# handheld-telefon.net
KiCad netlist of a schematic drawn in EAGLE
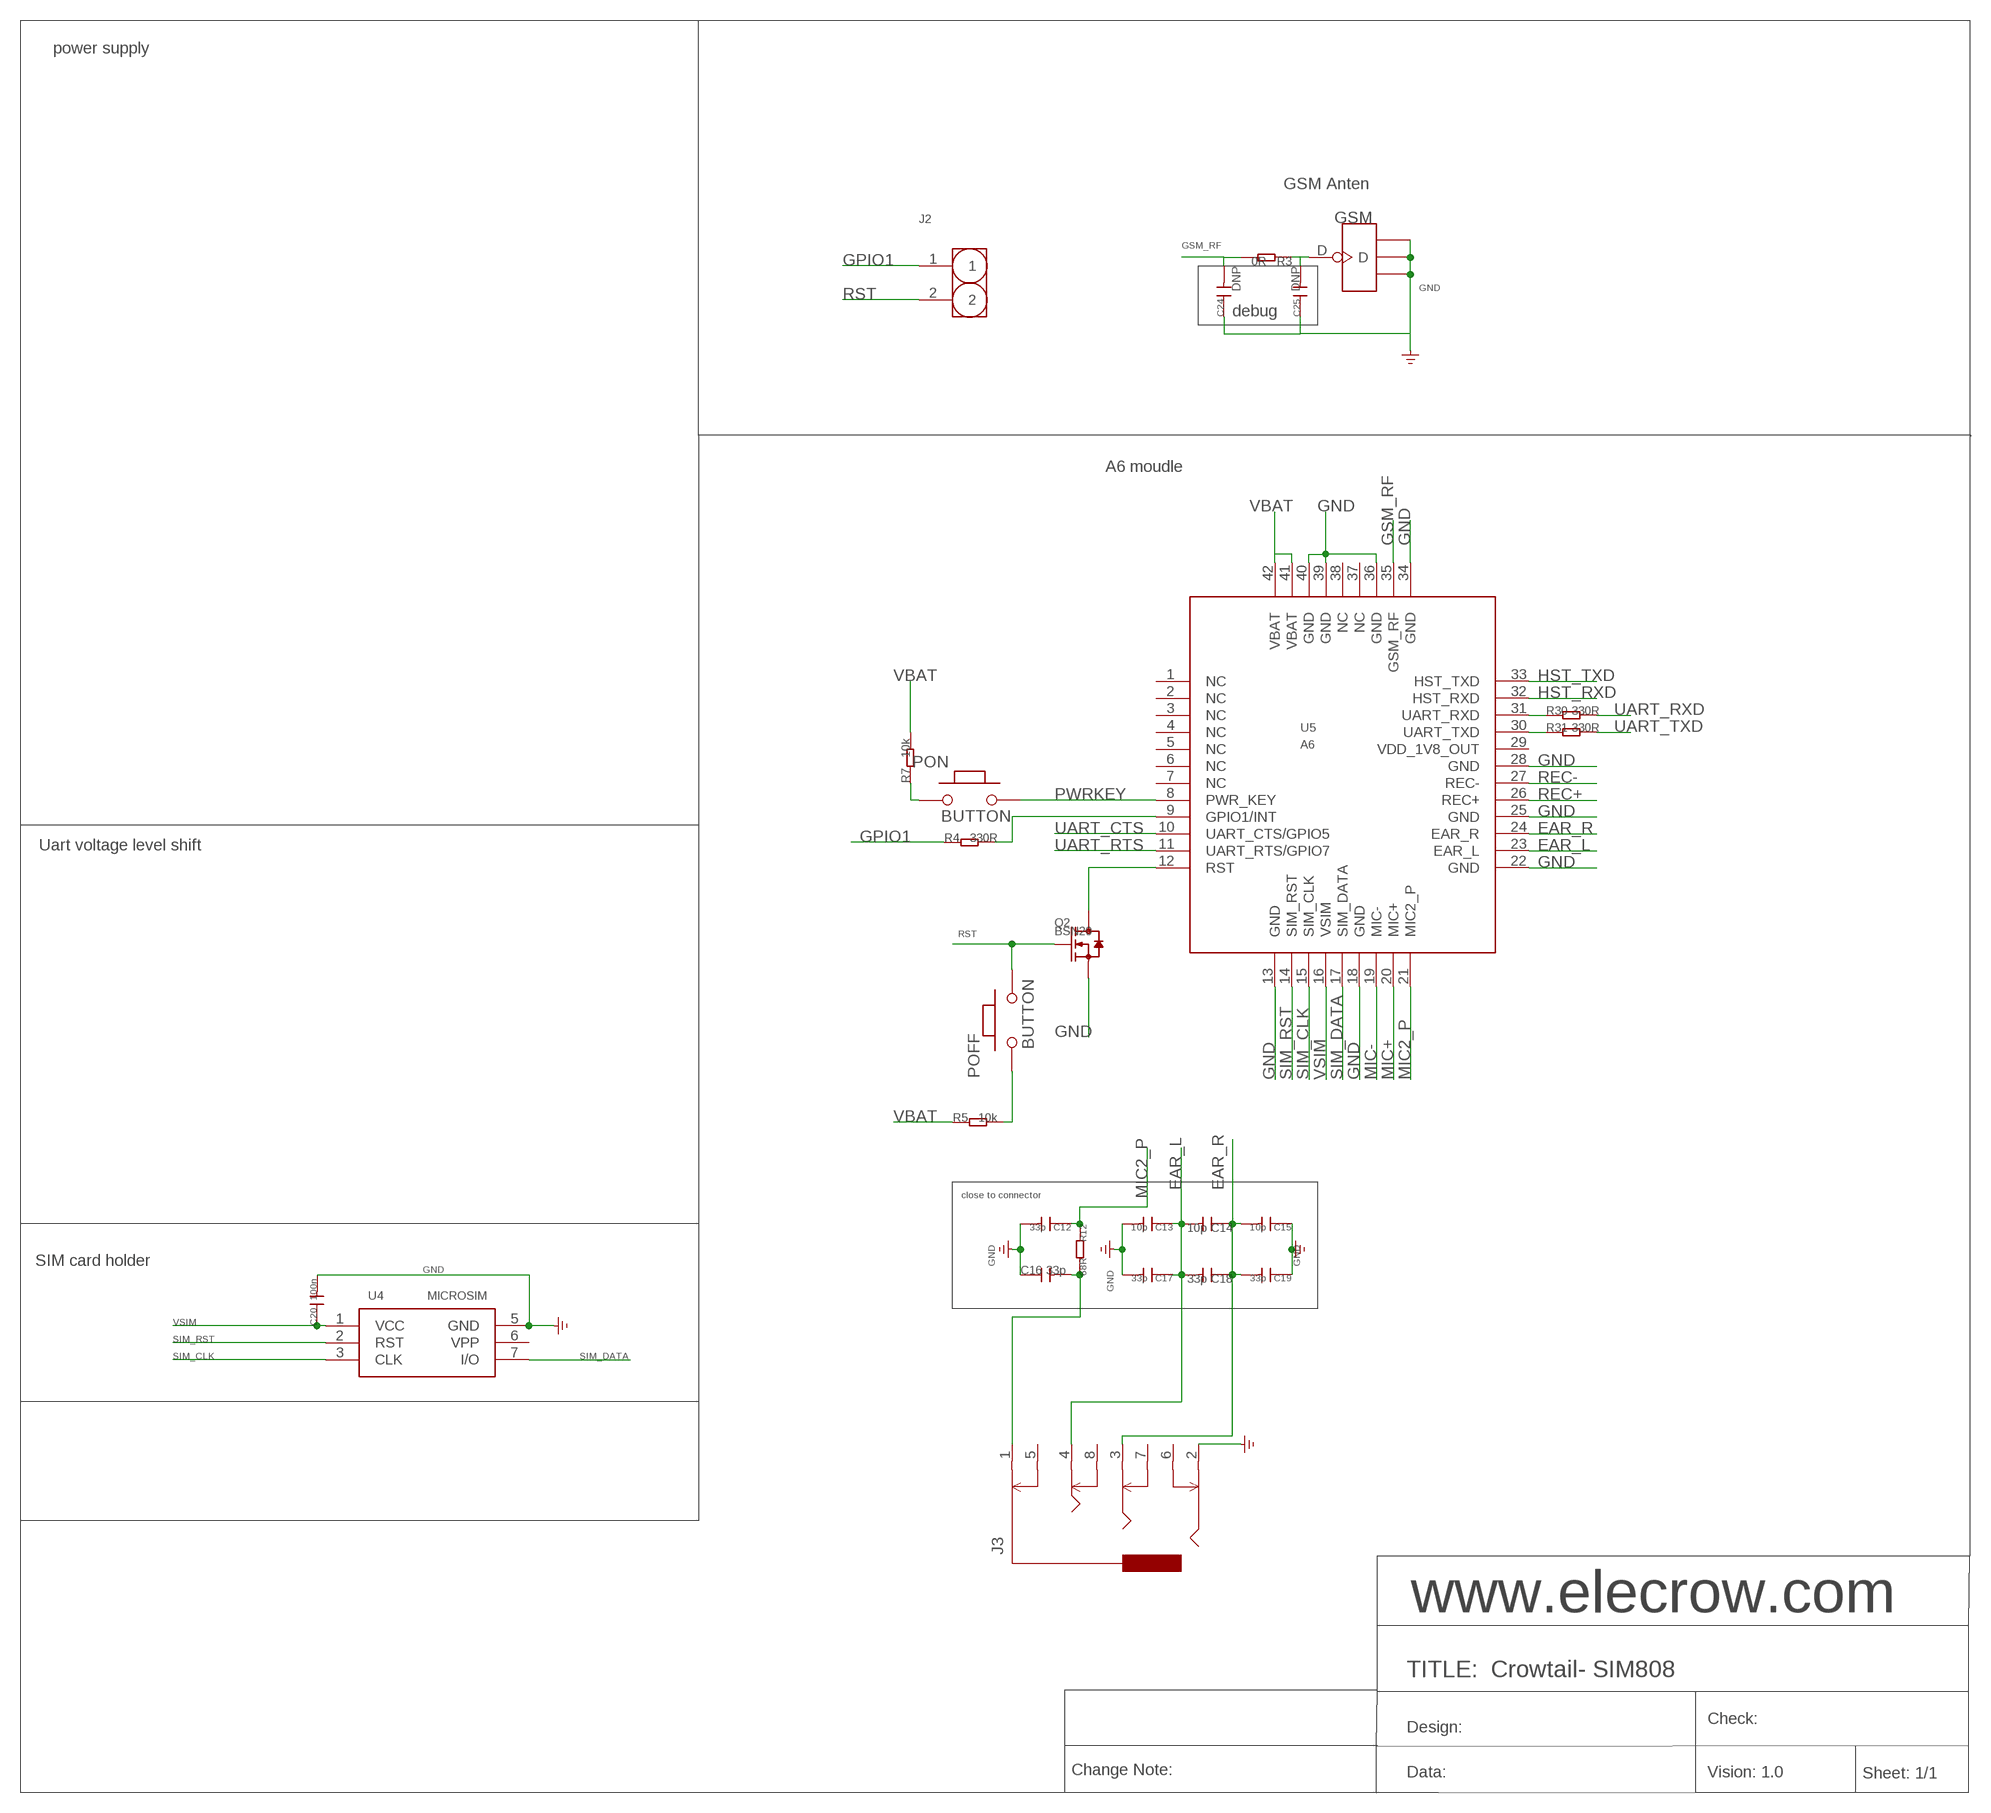
[diagram p0: schematic, sheet 1]

(export (version "E")
  (design (tool "Eeschema 10.0.6"))
  (components
    (comp (ref "C12")
      (value "33p")
      (footprint "eagle-import:C0603")
      (libsource (lib "eagle-import") (part "C-0603"))
    )
    (comp (ref "C13")
      (value "10p")
      (footprint "eagle-import:C0402")
      (libsource (lib "eagle-import") (part "C-0402"))
    )
    (comp (ref "C14")
      (value "10p")
      (footprint "eagle-import:C0402")
      (libsource (lib "eagle-import") (part "C-0402"))
    )
    (comp (ref "C15")
      (value "10p")
      (footprint "eagle-import:C0402")
      (libsource (lib "eagle-import") (part "C-0402"))
    )
    (comp (ref "C16")
      (value "33p")
      (footprint "eagle-import:C0603")
      (libsource (lib "eagle-import") (part "C-0603"))
    )
    (comp (ref "C17")
      (value "33p")
      (footprint "eagle-import:C0402")
      (libsource (lib "eagle-import") (part "C-0402"))
    )
    (comp (ref "C18")
      (value "33p")
      (footprint "eagle-import:C0402")
      (libsource (lib "eagle-import") (part "C-0402"))
    )
    (comp (ref "C19")
      (value "33p")
      (footprint "eagle-import:C0402")
      (libsource (lib "eagle-import") (part "C-0402"))
    )
    (comp (ref "C20")
      (value "100n")
      (footprint "eagle-import:C0603")
      (libsource (lib "eagle-import") (part "C-0603"))
    )
    (comp (ref "C24")
      (value "DNP")
      (footprint "eagle-import:C0402")
      (libsource (lib "eagle-import") (part "C-0402"))
    )
    (comp (ref "C25")
      (value "DNP")
      (footprint "eagle-import:C0402")
      (libsource (lib "eagle-import") (part "C-0402"))
    )
    (comp (ref "GSM")
      (value "ANTENNA-U-FL")
      (footprint "eagle-import:4P-U-FL")
      (libsource (lib "eagle-import") (part "ANTENNA-U-FL"))
    )
    (comp (ref "J2")
      (value "HEADER-2P-65/35MIL")
      (footprint "eagle-import:2P-2.54-65_35MIL")
      (libsource (lib "eagle-import") (part "HEADER-2P-65/35MIL"))
    )
    (comp (ref "J3")
      (value "AUDIO-8P'PJ-3536-L6S'")
      (footprint "eagle-import:8P-3.5-SMD")
      (libsource (lib "eagle-import") (part "AUDIO-8P'PJ-3536-L6S'"))
    )
    (comp (ref "POFF")
      (value "BUTTON")
      (footprint "eagle-import:157SW")
      (libsource (lib "eagle-import") (part "PB157"))
    )
    (comp (ref "PON")
      (value "BUTTON")
      (footprint "eagle-import:157SW")
      (libsource (lib "eagle-import") (part "PB157"))
    )
    (comp (ref "Q2")
      (value "BSN20")
      (footprint "eagle-import:SOT23")
      (libsource (lib "eagle-import") (part "MOSFET-N'SOT23'"))
    )
    (comp (ref "R3")
      (value "0R")
      (footprint "eagle-import:R0603")
      (libsource (lib "eagle-import") (part "R-0603"))
    )
    (comp (ref "R4")
      (value "330R")
      (footprint "eagle-import:R0603")
      (libsource (lib "eagle-import") (part "R-0603"))
    )
    (comp (ref "R5")
      (value "10k")
      (footprint "eagle-import:R0603")
      (libsource (lib "eagle-import") (part "R-0603"))
    )
    (comp (ref "R7")
      (value "10k")
      (footprint "eagle-import:R0603")
      (libsource (lib "eagle-import") (part "R-0603"))
    )
    (comp (ref "R12")
      (value "68R")
      (footprint "eagle-import:R0603")
      (libsource (lib "eagle-import") (part "R-0603"))
    )
    (comp (ref "R30")
      (value "330R")
      (footprint "eagle-import:R0603")
      (libsource (lib "eagle-import") (part "R-0603"))
    )
    (comp (ref "R31")
      (value "330R")
      (footprint "eagle-import:R0603")
      (libsource (lib "eagle-import") (part "R-0603"))
    )
    (comp (ref "U4")
      (value "MICROSIM")
      (footprint "eagle-import:MICROSIM")
      (libsource (lib "eagle-import") (part "MICROSIM"))
    )
    (comp (ref "U5") (value "A6") (footprint "eagle-import:A6") (libsource (lib "eagle-import") (part "A6")))
  )
  (nets
    (net (code "1") (name "/EAR_L") (class "Default")
      (node (ref "C13") (pin "1") (pinfunction "1_1") (pintype "passive"))
      (node (ref "C14") (pin "2") (pinfunction "2_2") (pintype "passive"))
      (node (ref "C17") (pin "1") (pinfunction "1_1") (pintype "passive"))
      (node (ref "C18") (pin "2") (pinfunction "2_2") (pintype "passive"))
      (node (ref "J3") (pin "4") (pinfunction "4_4") (pintype "bidirectional"))
      (node (ref "U5") (pin "23") (pinfunction "EAR_L_23") (pintype "bidirectional"))
    )
    (net (code "2") (name "/EAR_R") (class "Default")
      (node (ref "C14") (pin "1") (pinfunction "1_1") (pintype "passive"))
      (node (ref "C15") (pin "2") (pinfunction "2_2") (pintype "passive"))
      (node (ref "C18") (pin "1") (pinfunction "1_1") (pintype "passive"))
      (node (ref "C19") (pin "2") (pinfunction "2_2") (pintype "passive"))
      (node (ref "J3") (pin "3") (pinfunction "3_3") (pintype "bidirectional"))
      (node (ref "U5") (pin "24") (pinfunction "EAR_R_24") (pintype "bidirectional"))
    )
    (net (code "3") (name "/GPIO1") (class "Default")
      (node (ref "J2") (pin "1") (pinfunction "1_1") (pintype "bidirectional"))
      (node (ref "R4") (pin "1") (pinfunction "1_1") (pintype "passive"))
    )
    (net (code "4") (name "/GSM_RF") (class "Default")
      (node (ref "C24") (pin "2") (pinfunction "2_2") (pintype "passive"))
      (node (ref "R3") (pin "2") (pinfunction "2_2") (pintype "passive"))
      (node (ref "U5") (pin "35") (pinfunction "GSM_RF_35") (pintype "bidirectional"))
    )
    (net (code "5") (name "/HST_RXD") (class "Default")
      (node (ref "U5") (pin "32") (pinfunction "HST_RXD_32") (pintype "bidirectional"))
    )
    (net (code "6") (name "/HST_TXD") (class "Default")
      (node (ref "U5") (pin "33") (pinfunction "HST_TXD_33") (pintype "bidirectional"))
    )
    (net (code "7") (name "/MIC+") (class "Default")
      (node (ref "U5") (pin "20") (pinfunction "MIC+_20") (pintype "bidirectional"))
    )
    (net (code "8") (name "/MIC-") (class "Default")
      (node (ref "U5") (pin "19") (pinfunction "MIC-_19") (pintype "bidirectional"))
    )
    (net (code "9") (name "/MIC2_P") (class "Default")
      (node (ref "C12") (pin "1") (pinfunction "1_1") (pintype "passive"))
      (node (ref "R12") (pin "1") (pinfunction "1_1") (pintype "passive"))
      (node (ref "U5") (pin "21") (pinfunction "MIC2_P_21") (pintype "bidirectional"))
    )
    (net (code "10") (name "/PWRKEY") (class "Default")
      (node (ref "PON") (pin "2") (pinfunction "2_2") (pintype "passive"))
      (node (ref "U5") (pin "8") (pinfunction "PWR_KEY_8") (pintype "bidirectional"))
    )
    (net (code "11") (name "/REC+") (class "Default")
      (node (ref "U5") (pin "26") (pinfunction "REC+_26") (pintype "bidirectional"))
    )
    (net (code "12") (name "/REC-") (class "Default")
      (node (ref "U5") (pin "27") (pinfunction "REC-_27") (pintype "bidirectional"))
    )
    (net (code "13") (name "/RST") (class "Default")
      (node (ref "J2") (pin "2") (pinfunction "2_2") (pintype "bidirectional"))
      (node (ref "POFF") (pin "2") (pinfunction "2_2") (pintype "passive"))
      (node (ref "Q2") (pin "1") (pinfunction "G_1") (pintype "passive"))
    )
    (net (code "14") (name "/SIM_CLK") (class "Default")
      (node (ref "U4") (pin "3") (pinfunction "CLK_3") (pintype "bidirectional"))
      (node (ref "U5") (pin "15") (pinfunction "SIM_CLK_15") (pintype "bidirectional"))
    )
    (net (code "15") (name "/SIM_DATA") (class "Default")
      (node (ref "U4") (pin "7") (pinfunction "I/O_7") (pintype "bidirectional"))
      (node (ref "U5") (pin "17") (pinfunction "SIM_DATA_17") (pintype "bidirectional"))
    )
    (net (code "16") (name "/SIM_RST") (class "Default")
      (node (ref "U4") (pin "2") (pinfunction "RST_2") (pintype "bidirectional"))
      (node (ref "U5") (pin "14") (pinfunction "SIM_RST_14") (pintype "bidirectional"))
    )
    (net (code "17") (name "/UART_CTS") (class "Default")
      (node (ref "U5") (pin "10") (pinfunction "UART_CTS/GPIO5_10") (pintype "bidirectional"))
    )
    (net (code "18") (name "/UART_RTS") (class "Default")
      (node (ref "U5") (pin "11") (pinfunction "UART_RTS/GPIO7_11") (pintype "bidirectional"))
    )
    (net (code "19") (name "/UART_RXD") (class "Default")
      (node (ref "R30") (pin "2") (pinfunction "2_2") (pintype "passive"))
    )
    (net (code "20") (name "/UART_TXD") (class "Default")
      (node (ref "R31") (pin "2") (pinfunction "2_2") (pintype "passive"))
    )
    (net (code "21") (name "/VBAT") (class "Default")
      (node (ref "R5") (pin "1") (pinfunction "1_1") (pintype "passive"))
      (node (ref "R7") (pin "2") (pinfunction "2_2") (pintype "passive"))
      (node (ref "U5") (pin "41") (pinfunction "VBAT_41") (pintype "bidirectional"))
      (node (ref "U5") (pin "42") (pinfunction "VBAT_42") (pintype "bidirectional"))
    )
    (net (code "22") (name "/VSIM") (class "Default")
      (node (ref "C20") (pin "1") (pinfunction "1_1") (pintype "passive"))
      (node (ref "U4") (pin "1") (pinfunction "VCC_1") (pintype "bidirectional"))
      (node (ref "U5") (pin "16") (pinfunction "VSIM_16") (pintype "bidirectional"))
    )
    (net (code "23") (name "GND_POWER") (class "Default")
      (node (ref "C12") (pin "2") (pinfunction "2_2") (pintype "passive"))
      (node (ref "C13") (pin "2") (pinfunction "2_2") (pintype "passive"))
      (node (ref "C15") (pin "1") (pinfunction "1_1") (pintype "passive"))
      (node (ref "C16") (pin "1") (pinfunction "1_1") (pintype "passive"))
      (node (ref "C17") (pin "2") (pinfunction "2_2") (pintype "passive"))
      (node (ref "C19") (pin "1") (pinfunction "1_1") (pintype "passive"))
      (node (ref "C20") (pin "2") (pinfunction "2_2") (pintype "passive"))
      (node (ref "C24") (pin "1") (pinfunction "1_1") (pintype "passive"))
      (node (ref "C25") (pin "1") (pinfunction "1_1") (pintype "passive"))
      (node (ref "GSM") (pin "GND1") (pinfunction "GND1_GND1") (pintype "bidirectional"))
      (node (ref "GSM") (pin "GND2") (pinfunction "GND2_GND2") (pintype "bidirectional"))
      (node (ref "GSM") (pin "GND3") (pinfunction "GND3_GND3") (pintype "bidirectional"))
      (node (ref "J3") (pin "2") (pinfunction "2_2") (pintype "bidirectional"))
      (node (ref "Q2") (pin "2") (pinfunction "S_2") (pintype "passive"))
      (node (ref "U4") (pin "5") (pinfunction "GND_5") (pintype "bidirectional"))
      (node (ref "U5") (pin "13") (pinfunction "GND_13") (pintype "bidirectional"))
      (node (ref "U5") (pin "18") (pinfunction "GND_18") (pintype "bidirectional"))
      (node (ref "U5") (pin "22") (pinfunction "GND_22") (pintype "bidirectional"))
      (node (ref "U5") (pin "25") (pinfunction "GND_25") (pintype "bidirectional"))
      (node (ref "U5") (pin "28") (pinfunction "GND_28") (pintype "bidirectional"))
      (node (ref "U5") (pin "34") (pinfunction "GND_34") (pintype "bidirectional"))
      (node (ref "U5") (pin "36") (pinfunction "GND_36") (pintype "bidirectional"))
      (node (ref "U5") (pin "39") (pinfunction "GND_39") (pintype "bidirectional"))
      (node (ref "U5") (pin "40") (pinfunction "GND_40") (pintype "bidirectional"))
    )
    (net (code "24") (name "Net-(C16-Pad2)") (class "Default")
      (node (ref "C16") (pin "2") (pinfunction "2_2") (pintype "passive"))
      (node (ref "J3") (pin "1") (pinfunction "1_1") (pintype "bidirectional"))
      (node (ref "R12") (pin "2") (pinfunction "2_2") (pintype "passive"))
    )
    (net (code "25") (name "Net-(C25-Pad2)") (class "Default")
      (node (ref "C25") (pin "2") (pinfunction "2_2") (pintype "passive"))
      (node (ref "GSM") (pin "D") (pinfunction "D_D") (pintype "bidirectional"))
      (node (ref "R3") (pin "1") (pinfunction "1_1") (pintype "passive"))
    )
    (net (code "26") (name "Net-(POFF-Pad1)") (class "Default")
      (node (ref "POFF") (pin "1") (pinfunction "1_1") (pintype "passive"))
      (node (ref "R5") (pin "2") (pinfunction "2_2") (pintype "passive"))
    )
    (net (code "27") (name "Net-(PON-Pad1)") (class "Default")
      (node (ref "PON") (pin "1") (pinfunction "1_1") (pintype "passive"))
      (node (ref "R7") (pin "1") (pinfunction "1_1") (pintype "passive"))
    )
    (net (code "28") (name "Net-(Q2-D)") (class "Default")
      (node (ref "Q2") (pin "3") (pinfunction "D_3") (pintype "passive"))
      (node (ref "U5") (pin "12") (pinfunction "RST_12") (pintype "bidirectional"))
    )
    (net (code "29") (name "Net-(U5-GPIO1{slash}INT)") (class "Default")
      (node (ref "R4") (pin "2") (pinfunction "2_2") (pintype "passive"))
      (node (ref "U5") (pin "9") (pinfunction "GPIO1/INT_9") (pintype "bidirectional"))
    )
    (net (code "30") (name "Net-(U5-UART_RXD)") (class "Default")
      (node (ref "R30") (pin "1") (pinfunction "1_1") (pintype "passive"))
      (node (ref "U5") (pin "31") (pinfunction "UART_RXD_31") (pintype "bidirectional"))
    )
    (net (code "31") (name "Net-(U5-UART_TXD)") (class "Default")
      (node (ref "R31") (pin "1") (pinfunction "1_1") (pintype "passive"))
      (node (ref "U5") (pin "30") (pinfunction "UART_TXD_30") (pintype "bidirectional"))
    )
    (net (code "32") (name "unconnected-(J3-Pad5)") (class "Default")
      (node (ref "J3") (pin "5") (pinfunction "5_5") (pintype "bidirectional"))
    )
    (net (code "33") (name "unconnected-(J3-Pad6)") (class "Default")
      (node (ref "J3") (pin "6") (pinfunction "6_6") (pintype "bidirectional"))
    )
    (net (code "34") (name "unconnected-(J3-Pad7)") (class "Default")
      (node (ref "J3") (pin "7") (pinfunction "7_7") (pintype "bidirectional"))
    )
    (net (code "35") (name "unconnected-(J3-Pad8)") (class "Default")
      (node (ref "J3") (pin "8") (pinfunction "8_8") (pintype "bidirectional"))
    )
    (net (code "36") (name "unconnected-(U4-VPP-Pad6)") (class "Default")
      (node (ref "U4") (pin "6") (pinfunction "VPP_6") (pintype "bidirectional"))
    )
    (net (code "37") (name "unconnected-(U5-NC-Pad1)") (class "Default")
      (node (ref "U5") (pin "1") (pinfunction "NC_1") (pintype "bidirectional"))
    )
    (net (code "38") (name "unconnected-(U5-NC-Pad2)") (class "Default")
      (node (ref "U5") (pin "2") (pinfunction "NC_2") (pintype "bidirectional"))
    )
    (net (code "39") (name "unconnected-(U5-NC-Pad3)") (class "Default")
      (node (ref "U5") (pin "3") (pinfunction "NC_3") (pintype "bidirectional"))
    )
    (net (code "40") (name "unconnected-(U5-NC-Pad4)") (class "Default")
      (node (ref "U5") (pin "4") (pinfunction "NC_4") (pintype "bidirectional"))
    )
    (net (code "41") (name "unconnected-(U5-NC-Pad5)") (class "Default")
      (node (ref "U5") (pin "5") (pinfunction "NC_5") (pintype "bidirectional"))
    )
    (net (code "42") (name "unconnected-(U5-NC-Pad6)") (class "Default")
      (node (ref "U5") (pin "6") (pinfunction "NC_6") (pintype "bidirectional"))
    )
    (net (code "43") (name "unconnected-(U5-NC-Pad7)") (class "Default")
      (node (ref "U5") (pin "7") (pinfunction "NC_7") (pintype "bidirectional"))
    )
    (net (code "44") (name "unconnected-(U5-NC-Pad37)") (class "Default")
      (node (ref "U5") (pin "37") (pinfunction "NC_37") (pintype "bidirectional"))
    )
    (net (code "45") (name "unconnected-(U5-NC-Pad38)") (class "Default")
      (node (ref "U5") (pin "38") (pinfunction "NC_38") (pintype "bidirectional"))
    )
    (net (code "46") (name "unconnected-(U5-VDD_1V8_OUT-Pad29)") (class "Default")
      (node (ref "U5") (pin "29") (pinfunction "VDD_1V8_OUT_29") (pintype "bidirectional"))
    )
  )
)
